# HammerHacks_II_Badge_PCB.net
KiCad netlist of a schematic drawn in EasyEDA Pro
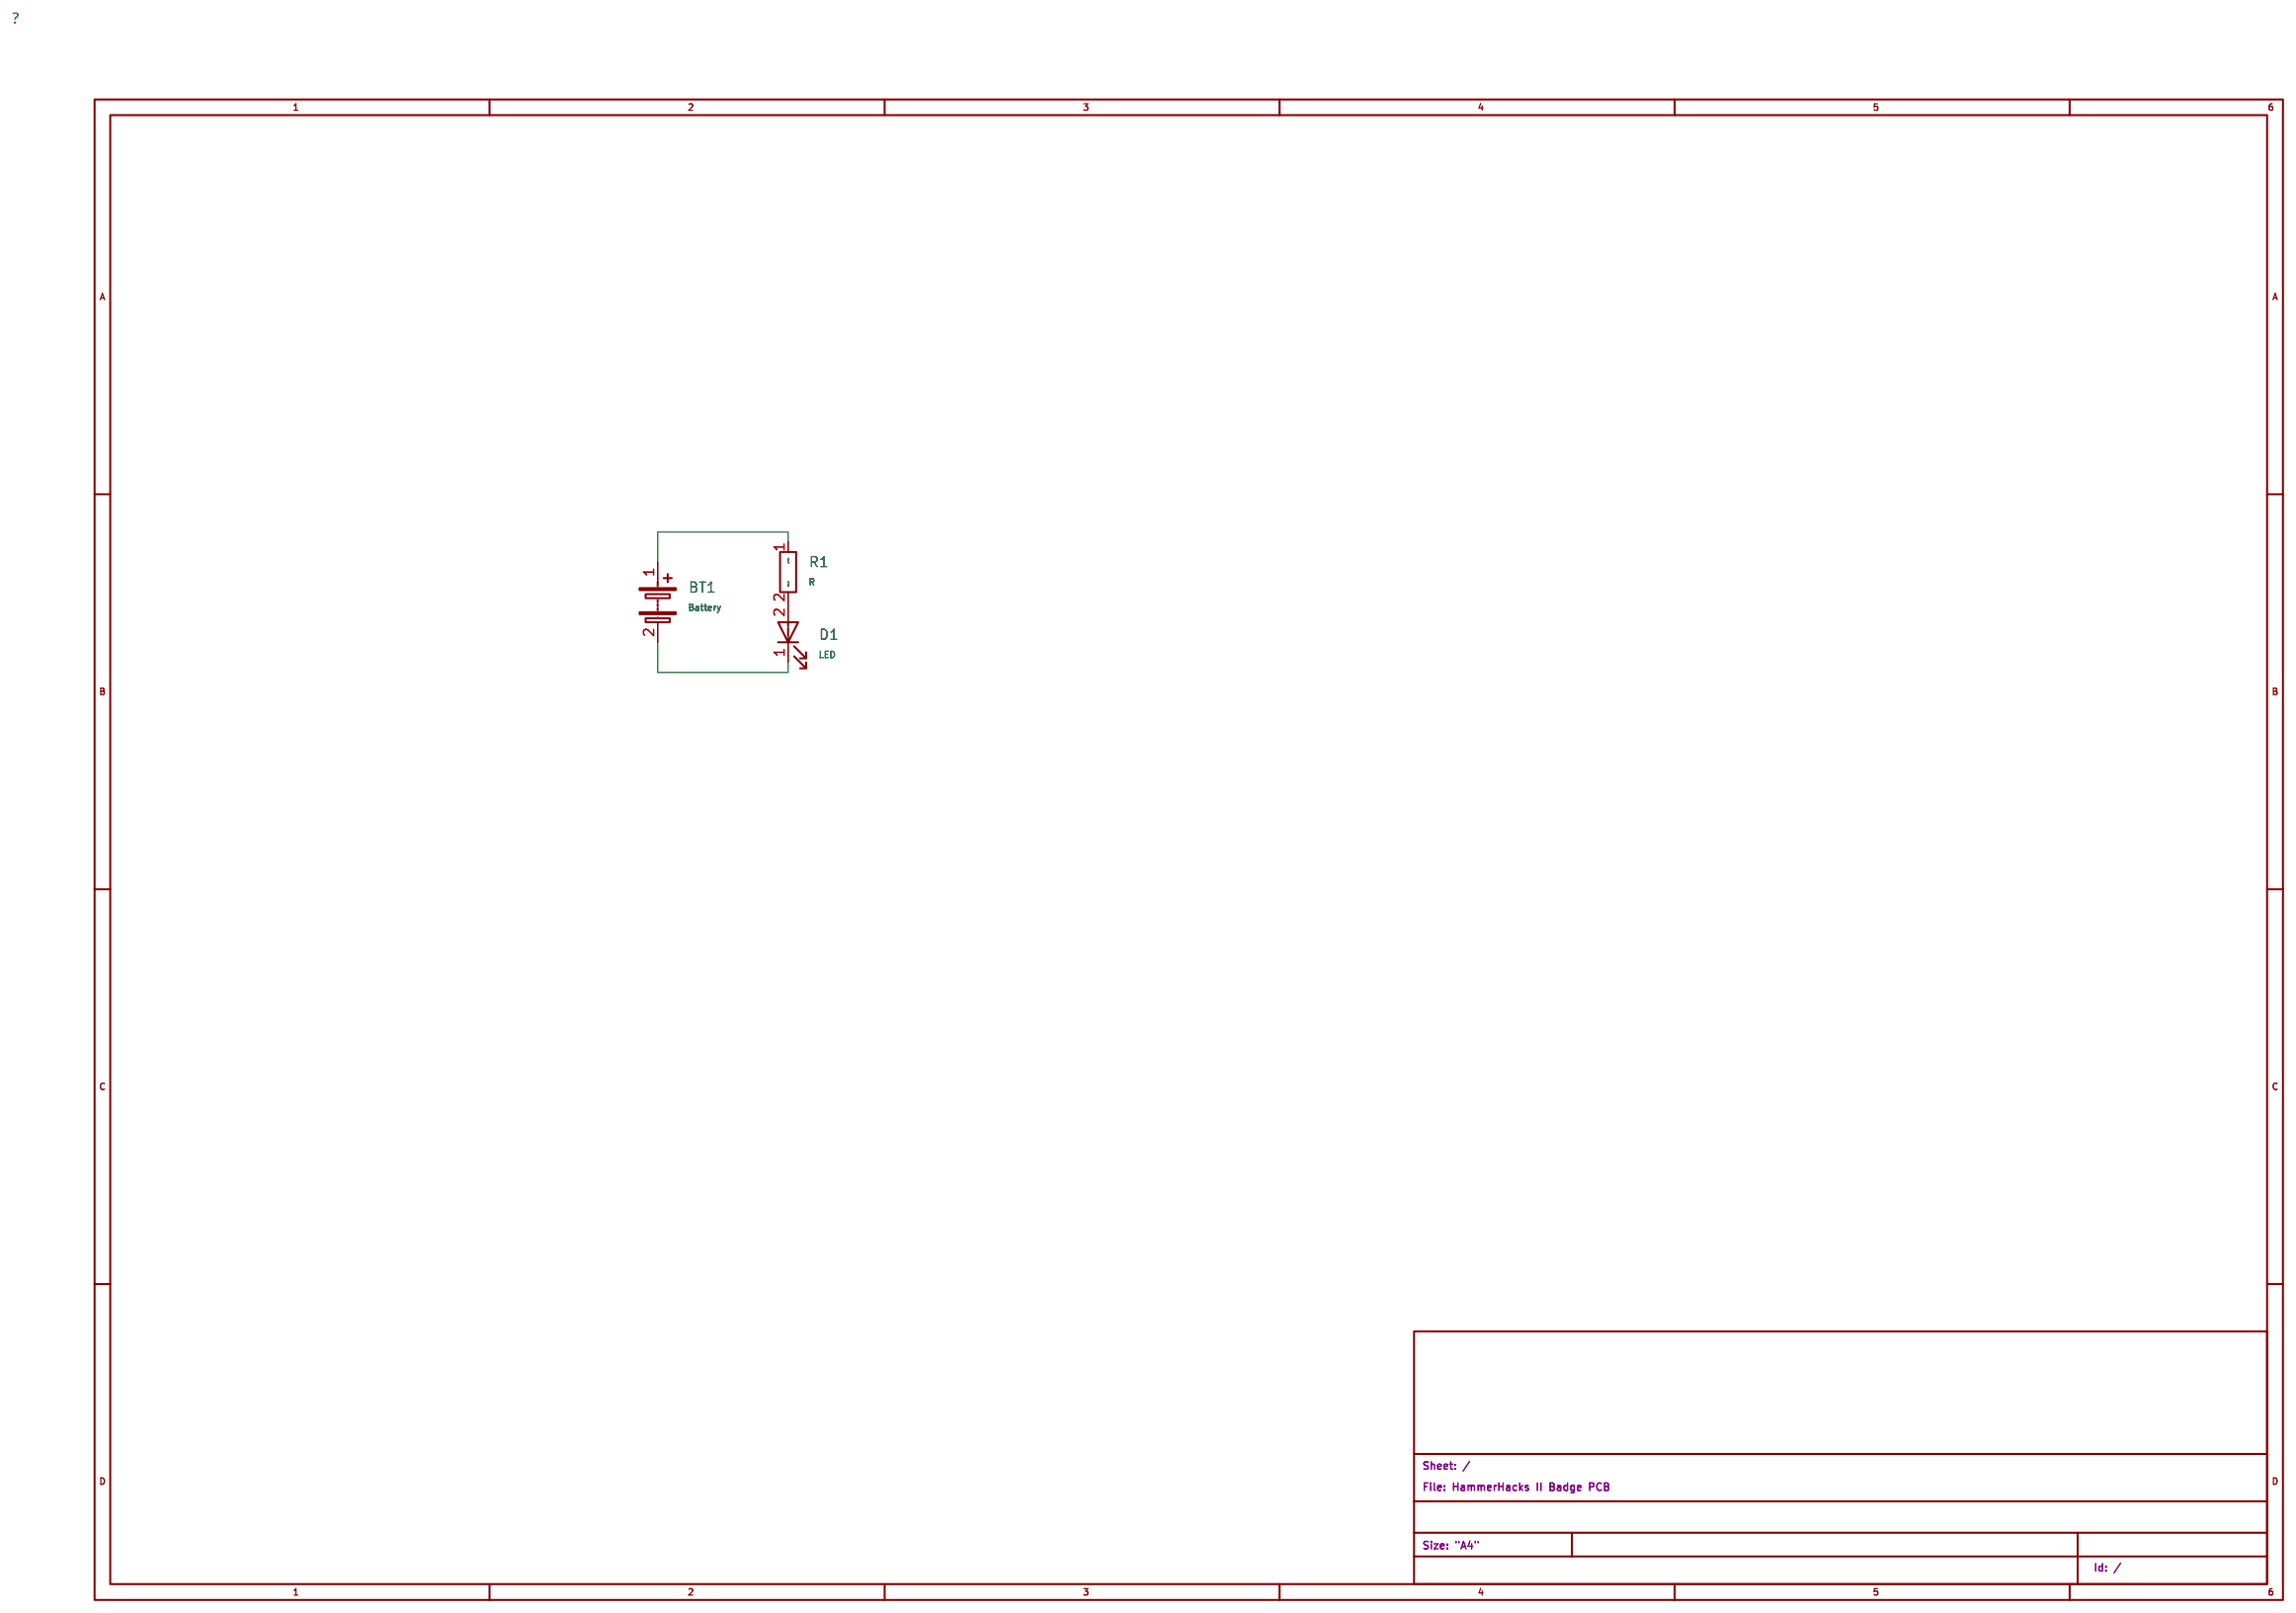
[diagram p0: schematic sheet]

(export (version "E")
  (design (tool "Eeschema 10.0.6"))
  (components
    (comp (ref "BT1")
      (value "Battery")
      (footprint "easyedapro:Battery:BatteryHolder_Keystone_3034_1x20mm")
      (description "Multiple-cell battery")
      (libsource (lib "easyedapro") (part "Device_Battery"))
    )
    (comp (ref "D1")
      (value "LED")
      (footprint "easyedapro:LED_THT:LED_D3.0mm")
      (description "Light emitting diode")
      (libsource (lib "easyedapro") (part "Device_LED"))
    )
    (comp (ref "R1")
      (value "R")
      (footprint "easyedapro:Resistor_THT:R_Axial_DIN0204_L3.6mm_D1.6mm_P5.08mm_Horizontal")
      (description "Resistor")
      (libsource (lib "easyedapro") (part "Device_R"))
    )
  )
  (nets
    (net (code "1") (name "Net-(BT1-+)") (class "Default")
      (node (ref "BT1") (pin "1") (pinfunction "+_1") (pintype "unspecified"))
      (node (ref "R1") (pin "1") (pinfunction "~_1") (pintype "unspecified"))
    )
    (net (code "2") (name "Net-(BT1--)") (class "Default")
      (node (ref "BT1") (pin "2") (pinfunction "-_2") (pintype "unspecified"))
      (node (ref "D1") (pin "1") (pinfunction "K_1") (pintype "unspecified"))
    )
    (net (code "3") (name "Net-(D1-A)") (class "Default")
      (node (ref "D1") (pin "2") (pinfunction "A_2") (pintype "unspecified"))
      (node (ref "R1") (pin "2") (pinfunction "~_2") (pintype "unspecified"))
    )
  )
)
